# IoTSchem.net
KiCad netlist of a schematic drawn in EAGLE
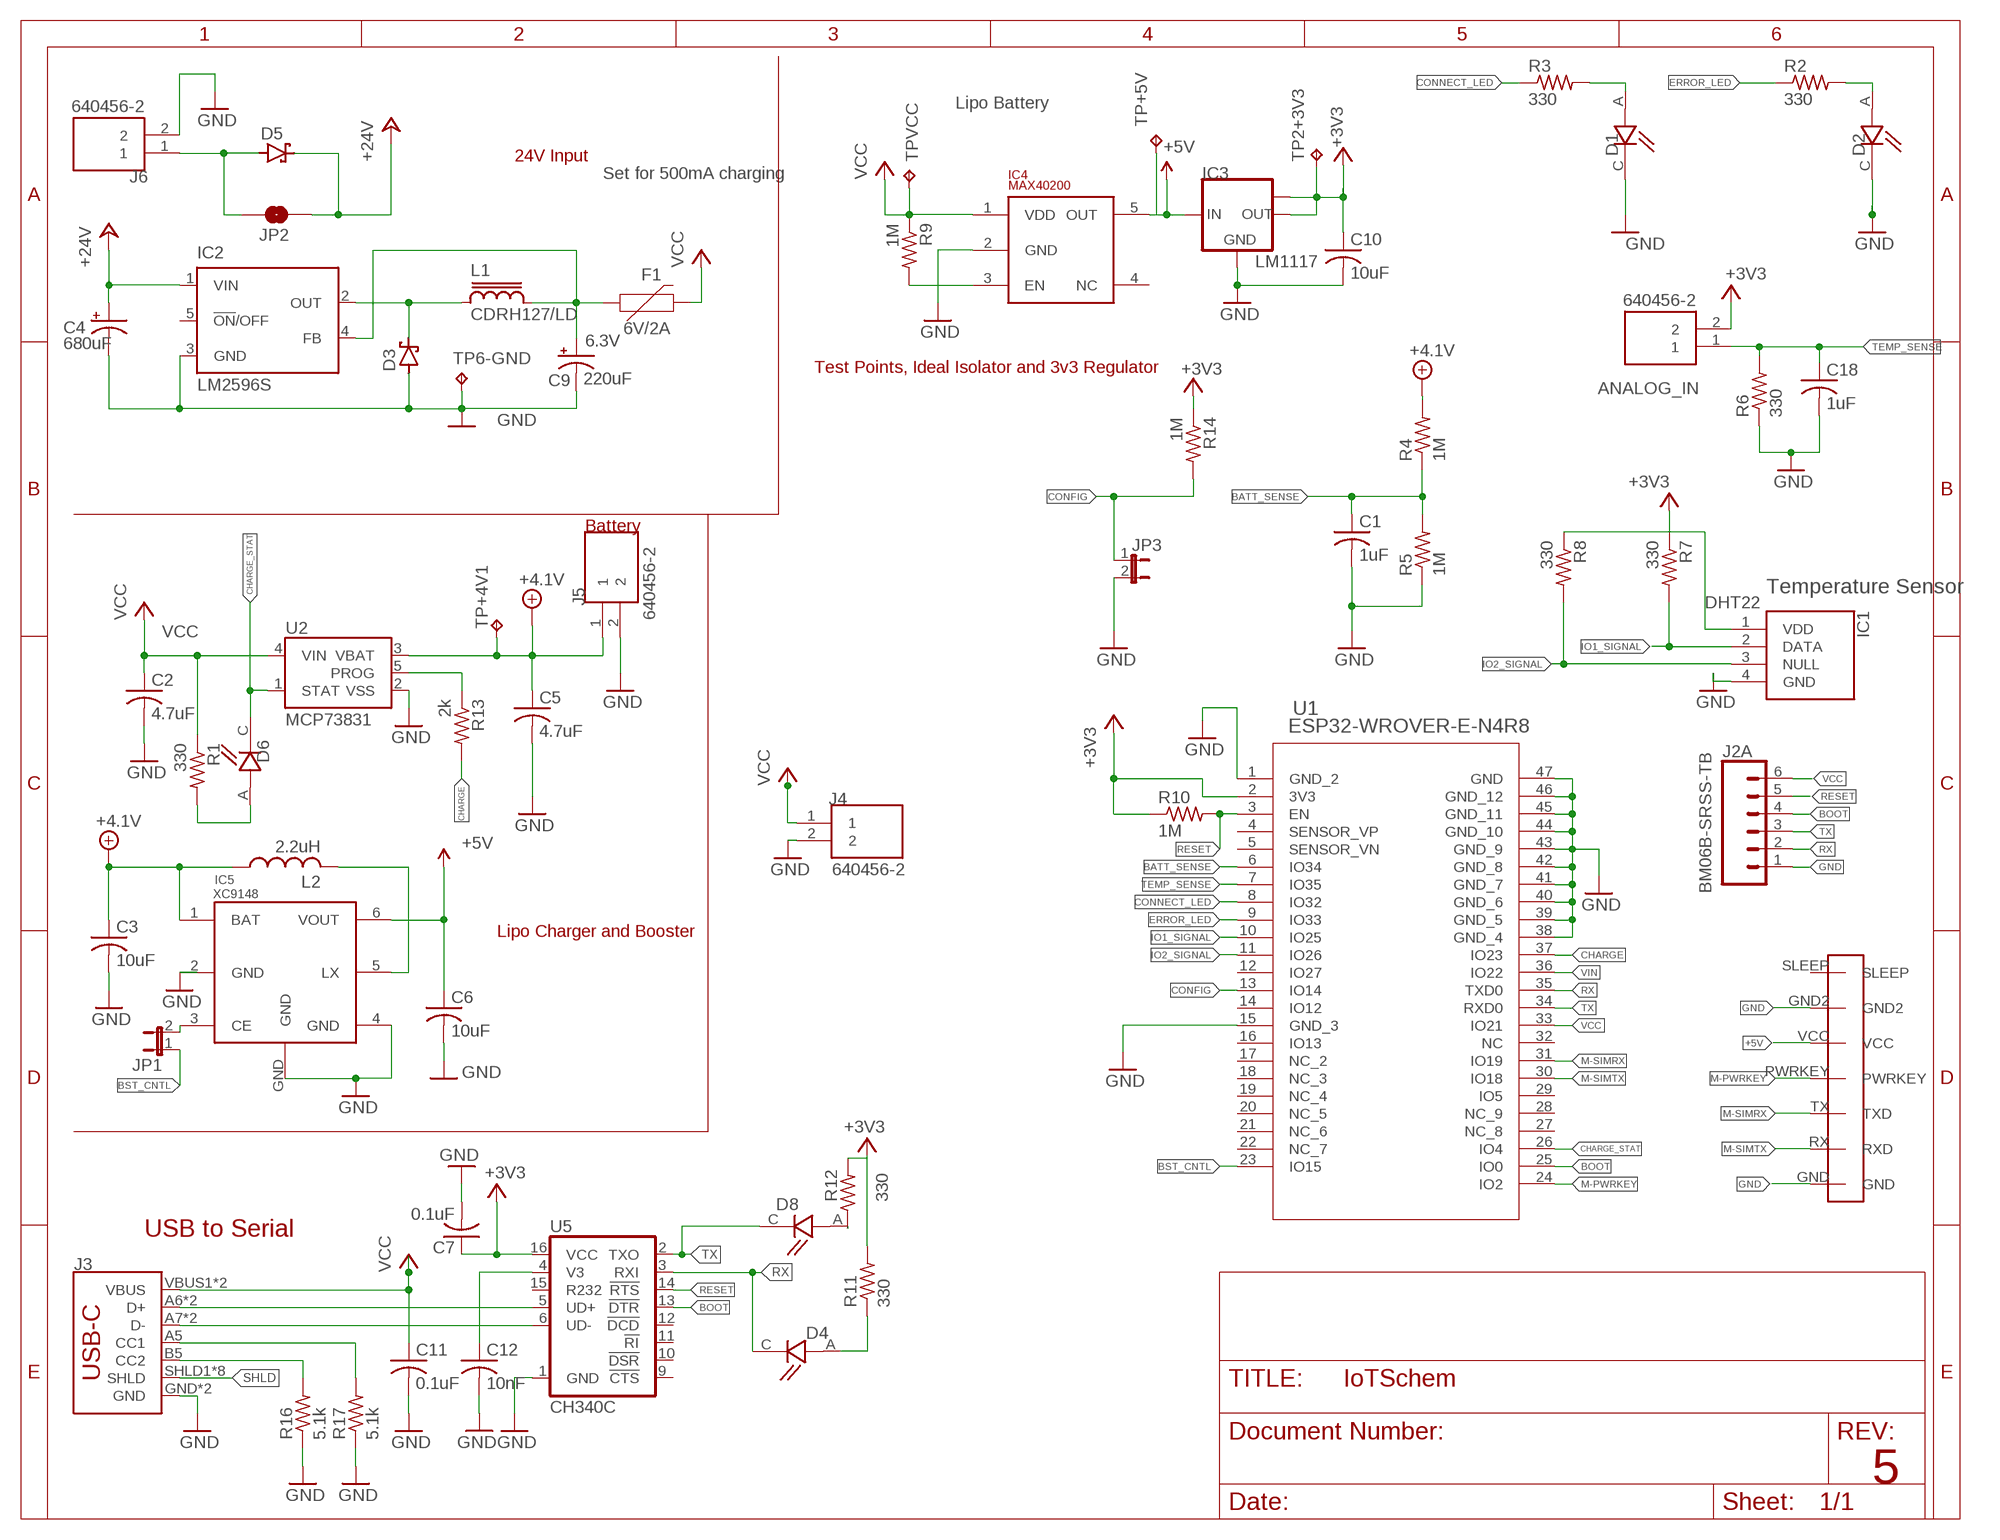
[diagram p0: schematic, sheet 1]

(export (version "E")
  (design (tool "Eeschema 10.0.6"))
  (components
    (comp (ref "ANALOG_IN")
      (value "640456-2")
      (footprint "eagle-import:TE_640456-2")
      (fields (field (name "DIGI-KEY_PART_NUMBER") "A1921-ND") (field (name "MF") "TE Connectivity"))
      (libsource (lib "eagle-import") (part "640456-2"))
    )
    (comp (ref "C1")
      (value "1uF")
      (footprint "eagle-import:C0805")
      (fields (field (name "DIGIKEYPART#") "311-1365-1-ND"))
      (libsource (lib "eagle-import") (part "C-USC0805"))
    )
    (comp (ref "C2")
      (value "4.7uF")
      (footprint "eagle-import:C0805")
      (fields (field (name "DIGIKEYPART#") "1276-6722-1-ND"))
      (libsource (lib "eagle-import") (part "C-USC0805"))
    )
    (comp (ref "C3")
      (value "10uF")
      (footprint "eagle-import:C0805")
      (fields (field (name "DIGIKEYPART#") "399-C0805C106K8PAC7800CT-ND"))
      (libsource (lib "eagle-import") (part "C-USC0805"))
    )
    (comp (ref "C4")
      (value "680uF")
      (footprint "eagle-import:E5-10,5")
      (fields (field (name "VOLTAGE") "25V"))
      (libsource (lib "eagle-import") (part "CPOL-USE5-10.5"))
    )
    (comp (ref "C5")
      (value "4.7uF")
      (footprint "eagle-import:C0805")
      (fields (field (name "DIGIKEYPART#") "1276-6722-1-ND"))
      (libsource (lib "eagle-import") (part "C-USC0805"))
    )
    (comp (ref "C6")
      (value "10uF")
      (footprint "eagle-import:C0805")
      (fields (field (name "DIGIKEYPART#") "399-C0805C106K8PAC7800CT-ND"))
      (libsource (lib "eagle-import") (part "C-USC0805"))
    )
    (comp (ref "C7")
      (value "0.1uF")
      (footprint "eagle-import:C0805")
      (fields (field (name "DIGIKEYPART#") "311-1140-1-ND"))
      (libsource (lib "eagle-import") (part "C-USC0805"))
    )
    (comp (ref "C9")
      (value "220uF")
      (footprint "eagle-import:UD-6,3X5,8_NICHICON")
      (fields (field (name "VOLTAGE") "6.3V"))
      (libsource (lib "eagle-import") (part "CPOL-USUD-6,3X5,8"))
    )
    (comp (ref "C10")
      (value "10uF")
      (footprint "eagle-import:C0805")
      (fields (field (name "DIGIKEYPART#") "399-C0805C106K8PAC7800CT-ND"))
      (libsource (lib "eagle-import") (part "C-USC0805"))
    )
    (comp (ref "C11")
      (value "0.1uF")
      (footprint "eagle-import:C0805")
      (fields (field (name "DIGIKEYPART#") "311-1140-1-ND"))
      (libsource (lib "eagle-import") (part "C-USC0805"))
    )
    (comp (ref "C12")
      (value "10nF")
      (footprint "eagle-import:C0805")
      (fields (field (name "DIGIKEYPART#") "1276-1015-1-ND"))
      (libsource (lib "eagle-import") (part "C-USC0805"))
    )
    (comp (ref "C18")
      (value "1uF")
      (footprint "eagle-import:C0805")
      (fields (field (name "DIGIKEYPART#") "311-1365-1-ND"))
      (libsource (lib "eagle-import") (part "C-USC0805"))
    )
    (comp (ref "D1")
      (value "5988170107F")
      (footprint "eagle-import:LEDC2012X70N")
      (fields (field (name "DIGI-KEY_PART_NUMBER") "350-2044-1-ND") (field (name "MF") "Dialight"))
      (libsource (lib "eagle-import") (part "5988170107F"))
    )
    (comp (ref "D2")
      (value "5988170107F")
      (footprint "eagle-import:LEDC2012X70N")
      (fields (field (name "DIGI-KEY_PART_NUMBER") "350-2044-1-ND") (field (name "MF") "Dialight"))
      (libsource (lib "eagle-import") (part "5988170107F"))
    )
    (comp (ref "D3")
      (value "SCHOTTKY-DIODESMD")
      (footprint "eagle-import:SMB")
      (libsource (lib "eagle-import") (part "SCHOTTKY-DIODESMD"))
    )
    (comp (ref "D4")
      (value "5988170107F")
      (footprint "eagle-import:LEDC2012X70N")
      (fields (field (name "DIGI-KEY_PART_NUMBER") "350-2044-1-ND") (field (name "MF") "Dialight"))
      (libsource (lib "eagle-import") (part "5988170107F"))
    )
    (comp (ref "D5")
      (value "1N4002")
      (footprint "eagle-import:SMB")
      (libsource (lib "eagle-import") (part "SCHOTTKY-DIODESMD"))
    )
    (comp (ref "D6")
      (value "5988170107F")
      (footprint "eagle-import:LEDC2012X70N")
      (fields (field (name "DIGI-KEY_PART_NUMBER") "350-2044-1-ND") (field (name "MF") "Dialight"))
      (libsource (lib "eagle-import") (part "5988170107F"))
    )
    (comp (ref "D8")
      (value "5988170107F")
      (footprint "eagle-import:LEDC2012X70N")
      (fields (field (name "DIGI-KEY_PART_NUMBER") "350-2044-1-ND") (field (name "MF") "Dialight"))
      (libsource (lib "eagle-import") (part "5988170107F"))
    )
    (comp (ref "F1")
      (value "6V/2A")
      (footprint "eagle-import:1210")
      (libsource (lib "eagle-import") (part "PPTC_6V2A"))
    )
    (comp (ref "IC1")
      (value "DHT22")
      (footprint "eagle-import:DHT22")
      (fields (field (name "DIGIKEYPART#") "1528-1504-ND"))
      (libsource (lib "eagle-import") (part "DHT22"))
    )
    (comp (ref "IC2")
      (value "LM2596S")
      (footprint "eagle-import:TO263-5")
      (fields
        (field (name "MF") "NATIONAL SEMICONDUCTOR")
        (field (name "MPN") "LM2596S-ADJ/NOPB")
        (field (name "DIGIKEYPART#") "2156-LM2596SX-5.0/NOPB-ND")
      )
      (libsource (lib "eagle-import") (part "LM2596S"))
    )
    (comp (ref "IC3")
      (value "LM1117MPX-3.3")
      (footprint "eagle-import:SOT223")
      (fields (field (name "DIGIKEYPART#") "LM1117IMP-3.3/NOPBCT-ND"))
      (libsource (lib "eagle-import") (part "LM1117MPX-3.3"))
    )
    (comp (ref "IC4")
      (value "MAX40200")
      (footprint "eagle-import:SOT23-5")
      (libsource (lib "eagle-import") (part "MAX40200"))
    )
    (comp (ref "IC5")
      (value "XC9148")
      (footprint "eagle-import:USP-6C")
      (fields (field (name "DIGIKEYPART#") "893-XC9148G50DER-GCT-ND "))
      (libsource (lib "eagle-import") (part "XC9148"))
    )
    (comp (ref "J1")
      (value "SIM7000A")
      (footprint "eagle-import:SIM7000A")
      (libsource (lib "eagle-import") (part "SIM7000A"))
    )
    (comp (ref "J2")
      (value "BM06B-SRSS-TB")
      (footprint "eagle-import:JST-6-SMD-HORI-1.0MM")
      (libsource (lib "eagle-import") (part "JST_6_PIN_HORIZONTAL"))
    )
    (comp (ref "J3")
      (value "USB_C16PIN")
      (footprint "eagle-import:USB-C-16P")
      (libsource (lib "eagle-import") (part "USB_C16PIN"))
    )
    (comp (ref "J4")
      (value "640456-2")
      (footprint "eagle-import:TE_640456-2")
      (fields (field (name "DIGI-KEY_PART_NUMBER") "A1921-ND") (field (name "MF") "TE Connectivity"))
      (libsource (lib "eagle-import") (part "640456-2"))
    )
    (comp (ref "J5")
      (value "640456-2")
      (footprint "eagle-import:TE_640456-2")
      (fields (field (name "DIGI-KEY_PART_NUMBER") "A1921-ND") (field (name "MF") "TE Connectivity"))
      (libsource (lib "eagle-import") (part "640456-2"))
    )
    (comp (ref "J6")
      (value "640456-2")
      (footprint "eagle-import:TE_640456-2")
      (fields (field (name "DIGI-KEY_PART_NUMBER") "A1921-ND") (field (name "MF") "TE Connectivity"))
      (libsource (lib "eagle-import") (part "640456-2"))
    )
    (comp (ref "JP1")
      (value "JP1E")
      (footprint "eagle-import:JP1")
      (libsource (lib "eagle-import") (part "JP1E"))
    )
    (comp (ref "JP2")
      (value "JUMPER-SMT_2_NO_SILK")
      (footprint "eagle-import:SMT-JUMPER_2_NO_SILK")
      (libsource (lib "eagle-import") (part "JUMPER-SMT_2_NO_SILK"))
    )
    (comp (ref "JP3")
      (value "JP1E")
      (footprint "eagle-import:JP1")
      (libsource (lib "eagle-import") (part "JP1E"))
    )
    (comp (ref "L1")
      (value "CDRH127/LD")
      (footprint "eagle-import:CDRH127_LD")
      (libsource (lib "eagle-import") (part "CDRH127/LD"))
    )
    (comp (ref "L2")
      (value "2.2uH")
      (footprint "eagle-import:L1812")
      (fields (field (name "DIGIKEYPART#") "490-12049-1-ND"))
      (libsource (lib "eagle-import") (part "L-USL1812"))
    )
    (comp (ref "R1")
      (value "330")
      (footprint "eagle-import:R0805")
      (libsource (lib "eagle-import") (part "R-US_R0805"))
    )
    (comp (ref "R2")
      (value "330")
      (footprint "eagle-import:R0805")
      (fields (field (name "DIGIKEYPART#") "RMCF0805JT330RCT-ND"))
      (libsource (lib "eagle-import") (part "R-US_R0805"))
    )
    (comp (ref "R3")
      (value "330")
      (footprint "eagle-import:R0805")
      (fields (field (name "DIGIKEYPART#") "RMCF0805JT330RCT-ND"))
      (libsource (lib "eagle-import") (part "R-US_R0805"))
    )
    (comp (ref "R4")
      (value "1M")
      (footprint "eagle-import:R0805")
      (fields (field (name "DIGIKEYPART#") "RMCF0805JT1M00CT-ND"))
      (libsource (lib "eagle-import") (part "R-US_R0805"))
    )
    (comp (ref "R5")
      (value "1M")
      (footprint "eagle-import:R0805")
      (fields (field (name "DIGIKEYPART#") "RMCF0805JT1M00CT-ND"))
      (libsource (lib "eagle-import") (part "R-US_R0805"))
    )
    (comp (ref "R6")
      (value "330")
      (footprint "eagle-import:R0805")
      (fields (field (name "DIGIKEYPART#") "RMCF0805JT330RCT-ND"))
      (libsource (lib "eagle-import") (part "R-US_R0805"))
    )
    (comp (ref "R7")
      (value "330")
      (footprint "eagle-import:R0805")
      (fields (field (name "DIGIKEYPART#") "RMCF0805JT330RCT-ND"))
      (libsource (lib "eagle-import") (part "R-US_R0805"))
    )
    (comp (ref "R8")
      (value "330")
      (footprint "eagle-import:R0805")
      (fields (field (name "DIGIKEYPART#") "RMCF0805JT330RCT-ND"))
      (libsource (lib "eagle-import") (part "R-US_R0805"))
    )
    (comp (ref "R9")
      (value "1M")
      (footprint "eagle-import:R0805")
      (fields (field (name "DIGIKEYPART#") "RMCF0805JT1M00CT-ND"))
      (libsource (lib "eagle-import") (part "R-US_R0805"))
    )
    (comp (ref "R10")
      (value "1M")
      (footprint "eagle-import:R0805")
      (fields (field (name "DIGIKEYPART#") "RMCF0805JT1M00CT-ND"))
      (libsource (lib "eagle-import") (part "R-US_R0805"))
    )
    (comp (ref "R11")
      (value "330")
      (footprint "eagle-import:R0805")
      (fields (field (name "DIGIKEYPART#") "RMCF0805JT330RCT-ND"))
      (libsource (lib "eagle-import") (part "R-US_R0805"))
    )
    (comp (ref "R12")
      (value "330")
      (footprint "eagle-import:R0805")
      (fields (field (name "DIGIKEYPART#") "RMCF0805JT330RCT-ND"))
      (libsource (lib "eagle-import") (part "R-US_R0805"))
    )
    (comp (ref "R13")
      (value "2k")
      (footprint "eagle-import:R0805")
      (fields (field (name "DIGIKEYPART#") "RMCF0805FT2K00CT-ND"))
      (libsource (lib "eagle-import") (part "R-US_R0805"))
    )
    (comp (ref "R14")
      (value "1M")
      (footprint "eagle-import:R0805")
      (fields (field (name "DIGIKEYPART#") "RMCF0805JT1M00CT-ND"))
      (libsource (lib "eagle-import") (part "R-US_R0805"))
    )
    (comp (ref "R16")
      (value "5.1k")
      (footprint "eagle-import:R0805")
      (fields (field (name "DIGIKEYPART#") "RMCF0805JT5K10CT-ND"))
      (libsource (lib "eagle-import") (part "R-US_R0805"))
    )
    (comp (ref "R17")
      (value "5.1k")
      (footprint "eagle-import:R0805")
      (fields (field (name "DIGIKEYPART#") "RMCF0805JT5K10CT-ND"))
      (libsource (lib "eagle-import") (part "R-US_R0805"))
    )
    (comp (ref "TP+4V1")
      (value "TPB1,27")
      (footprint "eagle-import:B1,27")
      (libsource (lib "eagle-import") (part "TPB1,27"))
    )
    (comp (ref "TP+5V")
      (value "TPB1,27")
      (footprint "eagle-import:B1,27")
      (libsource (lib "eagle-import") (part "TPB1,27"))
    )
    (comp (ref "TP2+3V3")
      (value "TPB1,27")
      (footprint "eagle-import:B1,27")
      (libsource (lib "eagle-import") (part "TPB1,27"))
    )
    (comp (ref "TP6-GND")
      (value "TPB1,27")
      (footprint "eagle-import:B1,27")
      (libsource (lib "eagle-import") (part "TPB1,27"))
    )
    (comp (ref "TPVCC")
      (value "TPB1,27")
      (footprint "eagle-import:B1,27")
      (libsource (lib "eagle-import") (part "TPB1,27"))
    )
    (comp (ref "U1")
      (value "ESP32-WROVER-E-N4R8")
      (footprint "eagle-import:ESP32­WROVER­E_ESP32­WROVER­IE")
      (fields (field (name "COPYRIGHT") "Copyright (C) 2022 Ultra Librarian. All rights reserved."))
      (libsource (lib "eagle-import") (part "ESP32-WROVER-E-N4R8"))
    )
    (comp (ref "U2")
      (value "MCP73831")
      (footprint "eagle-import:SOT23-5")
      (fields (field (name "DIGIKEYPART#") "MCP73831T-2DCI/OTCT-ND"))
      (libsource (lib "eagle-import") (part "MCP73831"))
    )
    (comp (ref "U5")
      (value "CH340C")
      (footprint "eagle-import:SO016")
      (libsource (lib "eagle-import") (part "CH340C"))
    )
  )
  (nets
    (net (code "1") (name "+3V3") (class "Default")
      (node (ref "ANALOG_IN") (pin "2") (pinfunction "2_2") (pintype "passive"))
      (node (ref "C10") (pin "1") (pinfunction "1_1") (pintype "passive"))
      (node (ref "C7") (pin "1") (pinfunction "1_1") (pintype "passive"))
      (node (ref "IC1") (pin "1") (pinfunction "VDD_1") (pintype "bidirectional"))
      (node (ref "IC3") (pin "2") (pinfunction "OUT_2") (pintype "passive"))
      (node (ref "IC3") (pin "TAB") (pinfunction "OUT1_TAB") (pintype "passive"))
      (node (ref "R10") (pin "1") (pinfunction "1_1") (pintype "passive"))
      (node (ref "R11") (pin "2") (pinfunction "2_2") (pintype "passive"))
      (node (ref "R12") (pin "2") (pinfunction "2_2") (pintype "passive"))
      (node (ref "R14") (pin "1") (pinfunction "1_1") (pintype "passive"))
      (node (ref "R7") (pin "1") (pinfunction "1_1") (pintype "passive"))
      (node (ref "R8") (pin "1") (pinfunction "1_1") (pintype "passive"))
      (node (ref "TP2+3V3") (pin "TP") (pinfunction "TP_TP") (pintype "input"))
      (node (ref "U1") (pin "2") (pinfunction "3V3_2") (pintype "power_in"))
      (node (ref "U5") (pin "16") (pinfunction "VCC_16") (pintype "bidirectional"))
    )
    (net (code "2") (name "+4.1V") (class "Default")
      (node (ref "C3") (pin "1") (pinfunction "1_1") (pintype "passive"))
      (node (ref "C5") (pin "1") (pinfunction "1_1") (pintype "passive"))
      (node (ref "IC5") (pin "1") (pinfunction "BAT_1") (pintype "bidirectional"))
      (node (ref "J5") (pin "1") (pinfunction "1_1") (pintype "passive"))
      (node (ref "L2") (pin "1") (pinfunction "1_1") (pintype "passive"))
      (node (ref "R4") (pin "2") (pinfunction "2_2") (pintype "passive"))
      (node (ref "TP+4V1") (pin "TP") (pinfunction "TP_TP") (pintype "input"))
      (node (ref "U2") (pin "3") (pinfunction "VBAT_3") (pintype "power_in"))
    )
    (net (code "3") (name "+5V") (class "Default")
      (node (ref "C6") (pin "1") (pinfunction "1_1") (pintype "passive"))
      (node (ref "IC3") (pin "3") (pinfunction "IN_3") (pintype "input"))
      (node (ref "IC4") (pin "5") (pinfunction "OUT_5") (pintype "bidirectional"))
      (node (ref "IC5") (pin "6") (pinfunction "VOUT_6") (pintype "bidirectional"))
      (node (ref "J1") (pin "VCC") (pinfunction "VCC_VCC") (pintype "bidirectional"))
      (node (ref "TP+5V") (pin "TP") (pinfunction "TP_TP") (pintype "input"))
    )
    (net (code "4") (name "+24V") (class "Default")
      (node (ref "C4") (pin "+") (pinfunction "+_+") (pintype "passive"))
      (node (ref "D5") (pin "C") (pinfunction "C_C") (pintype "passive"))
      (node (ref "IC2") (pin "1") (pinfunction "VIN_1") (pintype "input"))
      (node (ref "JP2") (pin "2") (pinfunction "2_2") (pintype "passive"))
    )
    (net (code "5") (name "BATT_SENSE") (class "Default")
      (node (ref "C1") (pin "1") (pinfunction "1_1") (pintype "passive"))
      (node (ref "R4") (pin "1") (pinfunction "1_1") (pintype "passive"))
      (node (ref "R5") (pin "2") (pinfunction "2_2") (pintype "passive"))
      (node (ref "U1") (pin "6") (pinfunction "IO34_6") (pintype "input"))
    )
    (net (code "6") (name "BOOT") (class "Default")
      (node (ref "J2") (pin "4") (pinfunction "4_4") (pintype "passive"))
      (node (ref "U1") (pin "25") (pinfunction "IO0_25") (pintype "bidirectional"))
      (node (ref "U5") (pin "13") (pinfunction "~{DTR}_13") (pintype "bidirectional"))
    )
    (net (code "7") (name "BST_CNTL") (class "Default")
      (node (ref "JP1") (pin "1") (pinfunction "1_1") (pintype "passive"))
      (node (ref "U1") (pin "23") (pinfunction "IO15_23") (pintype "bidirectional"))
    )
    (net (code "8") (name "CHARGE") (class "Default")
      (node (ref "R13") (pin "2") (pinfunction "2_2") (pintype "passive"))
      (node (ref "U1") (pin "37") (pinfunction "IO23_37") (pintype "bidirectional"))
    )
    (net (code "9") (name "CHARGE_STAT") (class "Default")
      (node (ref "D6") (pin "C") (pinfunction "C_C") (pintype "passive"))
      (node (ref "U1") (pin "26") (pinfunction "IO4_26") (pintype "bidirectional"))
      (node (ref "U2") (pin "1") (pinfunction "STAT_1") (pintype "output"))
    )
    (net (code "10") (name "CONFIG") (class "Default")
      (node (ref "JP3") (pin "1") (pinfunction "1_1") (pintype "passive"))
      (node (ref "R14") (pin "2") (pinfunction "2_2") (pintype "passive"))
      (node (ref "U1") (pin "13") (pinfunction "IO14_13") (pintype "bidirectional"))
    )
    (net (code "11") (name "CONNECT_LED") (class "Default")
      (node (ref "R3") (pin "1") (pinfunction "1_1") (pintype "passive"))
      (node (ref "U1") (pin "8") (pinfunction "IO32_8") (pintype "bidirectional"))
    )
    (net (code "12") (name "ERROR_LED") (class "Default")
      (node (ref "R2") (pin "1") (pinfunction "1_1") (pintype "passive"))
      (node (ref "U1") (pin "9") (pinfunction "IO33_9") (pintype "bidirectional"))
    )
    (net (code "13") (name "GND") (class "Default")
      (node (ref "C1") (pin "2") (pinfunction "2_2") (pintype "passive"))
      (node (ref "C10") (pin "2") (pinfunction "2_2") (pintype "passive"))
      (node (ref "C11") (pin "2") (pinfunction "2_2") (pintype "passive"))
      (node (ref "C12") (pin "2") (pinfunction "2_2") (pintype "passive"))
      (node (ref "C18") (pin "2") (pinfunction "2_2") (pintype "passive"))
      (node (ref "C2") (pin "2") (pinfunction "2_2") (pintype "passive"))
      (node (ref "C3") (pin "2") (pinfunction "2_2") (pintype "passive"))
      (node (ref "C4") (pin "-") (pinfunction "-_-") (pintype "passive"))
      (node (ref "C5") (pin "2") (pinfunction "2_2") (pintype "passive"))
      (node (ref "C6") (pin "2") (pinfunction "2_2") (pintype "passive"))
      (node (ref "C7") (pin "2") (pinfunction "2_2") (pintype "passive"))
      (node (ref "C9") (pin "-") (pinfunction "-_-") (pintype "passive"))
      (node (ref "D1") (pin "C") (pinfunction "C_C") (pintype "passive"))
      (node (ref "D2") (pin "C") (pinfunction "C_C") (pintype "passive"))
      (node (ref "D3") (pin "A") (pinfunction "A_A") (pintype "passive"))
      (node (ref "IC1") (pin "4") (pinfunction "GND_4") (pintype "bidirectional"))
      (node (ref "IC2") (pin "3") (pinfunction "GND_3") (pintype "power_in"))
      (node (ref "IC3") (pin "1") (pinfunction "GND_1") (pintype "input"))
      (node (ref "IC4") (pin "2") (pinfunction "GND_2") (pintype "bidirectional"))
      (node (ref "IC5") (pin "2") (pinfunction "GND_2") (pintype "bidirectional"))
      (node (ref "IC5") (pin "4") (pinfunction "GND_4") (pintype "bidirectional"))
      (node (ref "IC5") (pin "GND") (pinfunction "GND_GND") (pintype "bidirectional"))
      (node (ref "J1") (pin "GND") (pinfunction "GND_GND") (pintype "bidirectional"))
      (node (ref "J1") (pin "GND2") (pinfunction "GND2_GND2") (pintype "bidirectional"))
      (node (ref "J2") (pin "1") (pinfunction "1_1") (pintype "passive"))
      (node (ref "J3") (pin "GND") (pinfunction "GND_GND") (pintype "bidirectional"))
      (node (ref "J3") (pin "GND2") (pinfunction "GND_GND2") (pintype "bidirectional"))
      (node (ref "J4") (pin "2") (pinfunction "2_2") (pintype "passive"))
      (node (ref "J5") (pin "2") (pinfunction "2_2") (pintype "passive"))
      (node (ref "J6") (pin "2") (pinfunction "2_2") (pintype "passive"))
      (node (ref "JP3") (pin "2") (pinfunction "2_2") (pintype "passive"))
      (node (ref "R16") (pin "1") (pinfunction "1_1") (pintype "passive"))
      (node (ref "R17") (pin "1") (pinfunction "1_1") (pintype "passive"))
      (node (ref "R5") (pin "1") (pinfunction "1_1") (pintype "passive"))
      (node (ref "R6") (pin "1") (pinfunction "1_1") (pintype "passive"))
      (node (ref "TP6-GND") (pin "TP") (pinfunction "TP_TP") (pintype "input"))
      (node (ref "U1") (pin "1") (pinfunction "GND_2_1") (pintype "passive"))
      (node (ref "U1") (pin "15") (pinfunction "GND_3_15") (pintype "passive"))
      (node (ref "U1") (pin "38") (pinfunction "GND_4_38") (pintype "passive"))
      (node (ref "U1") (pin "39") (pinfunction "GND_5_39") (pintype "passive"))
      (node (ref "U1") (pin "40") (pinfunction "GND_6_40") (pintype "passive"))
      (node (ref "U1") (pin "41") (pinfunction "GND_7_41") (pintype "passive"))
      (node (ref "U1") (pin "42") (pinfunction "GND_8_42") (pintype "passive"))
      (node (ref "U1") (pin "43") (pinfunction "GND_9_43") (pintype "passive"))
      (node (ref "U1") (pin "44") (pinfunction "GND_10_44") (pintype "passive"))
      (node (ref "U1") (pin "45") (pinfunction "GND_11_45") (pintype "passive"))
      (node (ref "U1") (pin "46") (pinfunction "GND_12_46") (pintype "passive"))
      (node (ref "U1") (pin "47") (pinfunction "GND_47") (pintype "passive"))
      (node (ref "U2") (pin "2") (pinfunction "VSS_2") (pintype "power_in"))
      (node (ref "U5") (pin "1") (pinfunction "GND_1") (pintype "bidirectional"))
    )
    (net (code "14") (name "IO1_SIGNAL") (class "Default")
      (node (ref "IC1") (pin "2") (pinfunction "DATA_2") (pintype "bidirectional"))
      (node (ref "R7") (pin "2") (pinfunction "2_2") (pintype "passive"))
      (node (ref "U1") (pin "10") (pinfunction "IO25_10") (pintype "bidirectional"))
    )
    (net (code "15") (name "IO2_SIGNAL") (class "Default")
      (node (ref "IC1") (pin "3") (pinfunction "NULL_3") (pintype "bidirectional"))
      (node (ref "R8") (pin "2") (pinfunction "2_2") (pintype "passive"))
      (node (ref "U1") (pin "11") (pinfunction "IO26_11") (pintype "bidirectional"))
    )
    (net (code "16") (name "M-PWRKEY") (class "Default")
      (node (ref "J1") (pin "PWRKEY") (pinfunction "PWRKEY_PWRKEY") (pintype "bidirectional"))
      (node (ref "U1") (pin "24") (pinfunction "IO2_24") (pintype "bidirectional"))
    )
    (net (code "17") (name "M-SIMRX") (class "Default")
      (node (ref "J1") (pin "TX") (pinfunction "TXD_TX") (pintype "bidirectional"))
      (node (ref "U1") (pin "31") (pinfunction "IO19_31") (pintype "bidirectional"))
    )
    (net (code "18") (name "M-SIMTX") (class "Default")
      (node (ref "J1") (pin "RX") (pinfunction "RXD_RX") (pintype "bidirectional"))
      (node (ref "U1") (pin "30") (pinfunction "IO18_30") (pintype "bidirectional"))
    )
    (net (code "19") (name "Net-(D1-PadA)") (class "Default")
      (node (ref "D1") (pin "A") (pinfunction "A_A") (pintype "passive"))
      (node (ref "R3") (pin "2") (pinfunction "2_2") (pintype "passive"))
    )
    (net (code "20") (name "Net-(D2-PadA)") (class "Default")
      (node (ref "D2") (pin "A") (pinfunction "A_A") (pintype "passive"))
      (node (ref "R2") (pin "2") (pinfunction "2_2") (pintype "passive"))
    )
    (net (code "21") (name "Net-(D4-PadA)") (class "Default")
      (node (ref "D4") (pin "A") (pinfunction "A_A") (pintype "passive"))
      (node (ref "R11") (pin "1") (pinfunction "1_1") (pintype "passive"))
    )
    (net (code "22") (name "Net-(D5-PadA)") (class "Default")
      (node (ref "D5") (pin "A") (pinfunction "A_A") (pintype "passive"))
      (node (ref "J6") (pin "1") (pinfunction "1_1") (pintype "passive"))
      (node (ref "JP2") (pin "1") (pinfunction "1_1") (pintype "passive"))
    )
    (net (code "23") (name "Net-(D6-PadA)") (class "Default")
      (node (ref "D6") (pin "A") (pinfunction "A_A") (pintype "passive"))
      (node (ref "R1") (pin "2") (pinfunction "2_2") (pintype "passive"))
    )
    (net (code "24") (name "Net-(D8-PadA)") (class "Default")
      (node (ref "D8") (pin "A") (pinfunction "A_A") (pintype "passive"))
      (node (ref "R12") (pin "1") (pinfunction "1_1") (pintype "passive"))
    )
    (net (code "25") (name "Net-(IC2-FB)") (class "Default")
      (node (ref "C9") (pin "+") (pinfunction "+_+") (pintype "passive"))
      (node (ref "F1") (pin "1") (pinfunction "1_1") (pintype "bidirectional"))
      (node (ref "IC2") (pin "4") (pinfunction "FB_4") (pintype "input"))
      (node (ref "L1") (pin "2") (pinfunction "2_2") (pintype "passive"))
    )
    (net (code "26") (name "Net-(IC2-OUT)") (class "Default")
      (node (ref "D3") (pin "C") (pinfunction "C_C") (pintype "passive"))
      (node (ref "IC2") (pin "2") (pinfunction "OUT_2") (pintype "output"))
      (node (ref "L1") (pin "1") (pinfunction "1_1") (pintype "passive"))
    )
    (net (code "27") (name "Net-(IC4-EN)") (class "Default")
      (node (ref "IC4") (pin "3") (pinfunction "EN_3") (pintype "bidirectional"))
      (node (ref "R9") (pin "2") (pinfunction "2_2") (pintype "passive"))
    )
    (net (code "28") (name "Net-(IC5-CE)") (class "Default")
      (node (ref "IC5") (pin "3") (pinfunction "CE_3") (pintype "bidirectional"))
      (node (ref "JP1") (pin "2") (pinfunction "2_2") (pintype "passive"))
    )
    (net (code "29") (name "Net-(IC5-LX)") (class "Default")
      (node (ref "IC5") (pin "5") (pinfunction "LX_5") (pintype "bidirectional"))
      (node (ref "L2") (pin "2") (pinfunction "2_2") (pintype "passive"))
    )
    (net (code "30") (name "Net-(J3-CC1)") (class "Default")
      (node (ref "J3") (pin "A5") (pinfunction "CC1_A5") (pintype "bidirectional"))
      (node (ref "R17") (pin "2") (pinfunction "2_2") (pintype "passive"))
    )
    (net (code "31") (name "Net-(J3-CC2)") (class "Default")
      (node (ref "J3") (pin "B5") (pinfunction "CC2_B5") (pintype "bidirectional"))
      (node (ref "R16") (pin "2") (pinfunction "2_2") (pintype "passive"))
    )
    (net (code "32") (name "Net-(U2-PROG)") (class "Default")
      (node (ref "R13") (pin "1") (pinfunction "1_1") (pintype "passive"))
      (node (ref "U2") (pin "5") (pinfunction "PROG_5") (pintype "input"))
    )
    (net (code "33") (name "Net-(U5-UD+)") (class "Default")
      (node (ref "J3") (pin "A6") (pinfunction "D+_A6") (pintype "bidirectional"))
      (node (ref "J3") (pin "B6") (pinfunction "D+_B6") (pintype "bidirectional"))
      (node (ref "U5") (pin "5") (pinfunction "UD+_5") (pintype "bidirectional"))
    )
    (net (code "34") (name "Net-(U5-UD-)") (class "Default")
      (node (ref "J3") (pin "A7") (pinfunction "D-_A7") (pintype "bidirectional"))
      (node (ref "J3") (pin "B7") (pinfunction "D-_B7") (pintype "bidirectional"))
      (node (ref "U5") (pin "6") (pinfunction "UD-_6") (pintype "bidirectional"))
    )
    (net (code "35") (name "Net-(U5-V3)") (class "Default")
      (node (ref "C12") (pin "1") (pinfunction "1_1") (pintype "passive"))
      (node (ref "U5") (pin "4") (pinfunction "V3_4") (pintype "bidirectional"))
    )
    (net (code "36") (name "RESET") (class "Default")
      (node (ref "J2") (pin "5") (pinfunction "5_5") (pintype "passive"))
      (node (ref "R10") (pin "2") (pinfunction "2_2") (pintype "passive"))
      (node (ref "U1") (pin "3") (pinfunction "EN_3") (pintype "input"))
      (node (ref "U5") (pin "14") (pinfunction "~{RTS}_14") (pintype "bidirectional"))
    )
    (net (code "37") (name "RX") (class "Default")
      (node (ref "D4") (pin "C") (pinfunction "C_C") (pintype "passive"))
      (node (ref "J2") (pin "2") (pinfunction "2_2") (pintype "passive"))
      (node (ref "U1") (pin "35") (pinfunction "TXD0_35") (pintype "bidirectional"))
      (node (ref "U5") (pin "3") (pinfunction "RXI_3") (pintype "bidirectional"))
    )
    (net (code "38") (name "SHLD") (class "Default")
      (node (ref "J3") (pin "SHLD1") (pinfunction "SHLD_SHLD1") (pintype "bidirectional"))
      (node (ref "J3") (pin "SHLD2") (pinfunction "SHLD_SHLD2") (pintype "bidirectional"))
      (node (ref "J3") (pin "SHLD3") (pinfunction "SHLD_SHLD3") (pintype "bidirectional"))
      (node (ref "J3") (pin "SHLD4") (pinfunction "SHLD_SHLD4") (pintype "bidirectional"))
      (node (ref "J3") (pin "SHLD5") (pinfunction "SHLD_SHLD5") (pintype "bidirectional"))
      (node (ref "J3") (pin "SHLD6") (pinfunction "SHLD_SHLD6") (pintype "bidirectional"))
      (node (ref "J3") (pin "SHLD7") (pinfunction "SHLD_SHLD7") (pintype "bidirectional"))
      (node (ref "J3") (pin "SHLD8") (pinfunction "SHLD_SHLD8") (pintype "bidirectional"))
    )
    (net (code "39") (name "TEMP_SENSE") (class "Default")
      (node (ref "ANALOG_IN") (pin "1") (pinfunction "1_1") (pintype "passive"))
      (node (ref "C18") (pin "1") (pinfunction "1_1") (pintype "passive"))
      (node (ref "R6") (pin "2") (pinfunction "2_2") (pintype "passive"))
      (node (ref "U1") (pin "7") (pinfunction "IO35_7") (pintype "input"))
    )
    (net (code "40") (name "TX") (class "Default")
      (node (ref "D8") (pin "C") (pinfunction "C_C") (pintype "passive"))
      (node (ref "J2") (pin "3") (pinfunction "3_3") (pintype "passive"))
      (node (ref "U1") (pin "34") (pinfunction "RXD0_34") (pintype "bidirectional"))
      (node (ref "U5") (pin "2") (pinfunction "TXO_2") (pintype "bidirectional"))
    )
    (net (code "41") (name "VCC") (class "Default")
      (node (ref "C11") (pin "1") (pinfunction "1_1") (pintype "passive"))
      (node (ref "C2") (pin "1") (pinfunction "1_1") (pintype "passive"))
      (node (ref "F1") (pin "2") (pinfunction "2_2") (pintype "bidirectional"))
      (node (ref "IC4") (pin "1") (pinfunction "VDD_1") (pintype "bidirectional"))
      (node (ref "J2") (pin "6") (pinfunction "6_6") (pintype "passive"))
      (node (ref "J3") (pin "VBUS1") (pinfunction "VBUS_VBUS1") (pintype "bidirectional"))
      (node (ref "J3") (pin "VBUS2") (pinfunction "VBUS_VBUS2") (pintype "bidirectional"))
      (node (ref "J4") (pin "1") (pinfunction "1_1") (pintype "passive"))
      (node (ref "R1") (pin "1") (pinfunction "1_1") (pintype "passive"))
      (node (ref "R9") (pin "1") (pinfunction "1_1") (pintype "passive"))
      (node (ref "TPVCC") (pin "TP") (pinfunction "TP_TP") (pintype "input"))
      (node (ref "U1") (pin "33") (pinfunction "IO21_33") (pintype "bidirectional"))
      (node (ref "U2") (pin "4") (pinfunction "VIN_4") (pintype "power_in"))
    )
    (net (code "42") (name "VIN") (class "Default")
      (node (ref "U1") (pin "36") (pinfunction "IO22_36") (pintype "bidirectional"))
    )
    (net (code "43") (name "unconnected-(IC2-~{ON}{slash}OFF-Pad5)") (class "Default")
      (node (ref "IC2") (pin "5") (pinfunction "~{ON}/OFF_5") (pintype "input"))
    )
    (net (code "44") (name "unconnected-(IC4-NC-Pad4)") (class "Default")
      (node (ref "IC4") (pin "4") (pinfunction "NC_4") (pintype "bidirectional"))
    )
    (net (code "45") (name "unconnected-(J1-PadSLEEP)") (class "Default")
      (node (ref "J1") (pin "SLEEP") (pinfunction "SLEEP_SLEEP") (pintype "bidirectional"))
    )
    (net (code "46") (name "unconnected-(U1-IO5-Pad29)") (class "Default")
      (node (ref "U1") (pin "29") (pinfunction "IO5_29") (pintype "bidirectional"))
    )
    (net (code "47") (name "unconnected-(U1-IO12-Pad14)") (class "Default")
      (node (ref "U1") (pin "14") (pinfunction "IO12_14") (pintype "bidirectional"))
    )
    (net (code "48") (name "unconnected-(U1-IO13-Pad16)") (class "Default")
      (node (ref "U1") (pin "16") (pinfunction "IO13_16") (pintype "bidirectional"))
    )
    (net (code "49") (name "unconnected-(U1-IO27-Pad12)") (class "Default")
      (node (ref "U1") (pin "12") (pinfunction "IO27_12") (pintype "bidirectional"))
    )
    (net (code "50") (name "unconnected-(U1-NC-Pad32)") (class "Default")
      (node (ref "U1") (pin "32") (pinfunction "NC_32") (pintype "no_connect"))
    )
    (net (code "51") (name "unconnected-(U1-NC_2-Pad17)") (class "Default")
      (node (ref "U1") (pin "17") (pinfunction "NC_2_17") (pintype "no_connect"))
    )
    (net (code "52") (name "unconnected-(U1-NC_3-Pad18)") (class "Default")
      (node (ref "U1") (pin "18") (pinfunction "NC_3_18") (pintype "no_connect"))
    )
    (net (code "53") (name "unconnected-(U1-NC_4-Pad19)") (class "Default")
      (node (ref "U1") (pin "19") (pinfunction "NC_4_19") (pintype "no_connect"))
    )
    (net (code "54") (name "unconnected-(U1-NC_5-Pad20)") (class "Default")
      (node (ref "U1") (pin "20") (pinfunction "NC_5_20") (pintype "no_connect"))
    )
    (net (code "55") (name "unconnected-(U1-NC_6-Pad21)") (class "Default")
      (node (ref "U1") (pin "21") (pinfunction "NC_6_21") (pintype "no_connect"))
    )
    (net (code "56") (name "unconnected-(U1-NC_7-Pad22)") (class "Default")
      (node (ref "U1") (pin "22") (pinfunction "NC_7_22") (pintype "no_connect"))
    )
    (net (code "57") (name "unconnected-(U1-NC_8-Pad27)") (class "Default")
      (node (ref "U1") (pin "27") (pinfunction "NC_8_27") (pintype "no_connect"))
    )
    (net (code "58") (name "unconnected-(U1-NC_9-Pad28)") (class "Default")
      (node (ref "U1") (pin "28") (pinfunction "NC_9_28") (pintype "no_connect"))
    )
    (net (code "59") (name "unconnected-(U1-SENSOR_VN-Pad5)") (class "Default")
      (node (ref "U1") (pin "5") (pinfunction "SENSOR_VN_5") (pintype "input"))
    )
    (net (code "60") (name "unconnected-(U1-SENSOR_VP-Pad4)") (class "Default")
      (node (ref "U1") (pin "4") (pinfunction "SENSOR_VP_4") (pintype "input"))
    )
    (net (code "61") (name "unconnected-(U5-R232-Pad15)") (class "Default")
      (node (ref "U5") (pin "15") (pinfunction "R232_15") (pintype "bidirectional"))
    )
    (net (code "62") (name "unconnected-(U5-~{CTS}-Pad9)") (class "Default")
      (node (ref "U5") (pin "9") (pinfunction "~{CTS}_9") (pintype "bidirectional"))
    )
    (net (code "63") (name "unconnected-(U5-~{DCD}-Pad12)") (class "Default")
      (node (ref "U5") (pin "12") (pinfunction "~{DCD}_12") (pintype "bidirectional"))
    )
    (net (code "64") (name "unconnected-(U5-~{DSR}-Pad10)") (class "Default")
      (node (ref "U5") (pin "10") (pinfunction "~{DSR}_10") (pintype "bidirectional"))
    )
    (net (code "65") (name "unconnected-(U5-~{RI}-Pad11)") (class "Default")
      (node (ref "U5") (pin "11") (pinfunction "~{RI}_11") (pintype "bidirectional"))
    )
  )
)
